# ProPrj_Transist_rle_Led_Kontrol_Devresi_.net
KiCad netlist of a schematic drawn in EasyEDA Pro
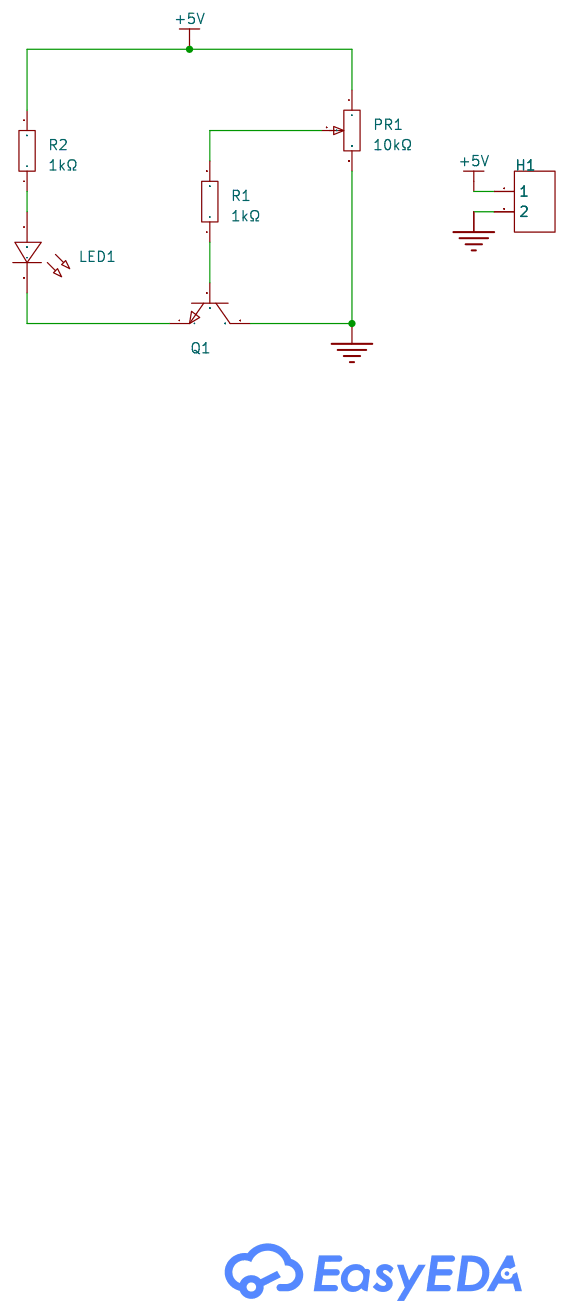
[diagram p0: schematic sheet]

(export (version "E")
  (design (tool "Eeschema 10.0.6"))
  (components
    (comp (ref "H1")
      (value "~")
      (footprint "easyedapro:HDR-TH_2P-P2.54-V-F")
      (fields (field (name "Manufacturer Part") "2.54-1*2P母") (field (name "Manufacturer") "BOOMELE(博穆精密)"))
      (libsource (lib "easyedapro") (part "Header-Female-2.54_1x2"))
    )
    (comp (ref "LED1")
      (value "~")
      (footprint "easyedapro:LED_TH-3mm")
      (libsource (lib "easyedapro") (part "LED_TH-R"))
    )
    (comp (ref "PR1")
      (value "10kΩ")
      (footprint "easyedapro:R_3296")
      (libsource (lib "easyedapro") (part "R_3296"))
    )
    (comp (ref "Q1")
      (value "~")
      (footprint "easyedapro:S8050_TO_92")
      (libsource (lib "easyedapro") (part "S8050_TO_NPN"))
    )
    (comp (ref "R1")
      (value "1kΩ")
      (footprint "easyedapro:Res_1/4W")
      (libsource (lib "easyedapro") (part "电阻"))
    )
    (comp (ref "R2")
      (value "1kΩ")
      (footprint "easyedapro:Res_1/4W")
      (libsource (lib "easyedapro") (part "电阻"))
    )
  )
  (nets
    (net (code "1") (name "+5V") (class "Default")
      (node (ref "H1") (pin "1") (pinfunction "1_1") (pintype "input"))
      (node (ref "PR1") (pin "1") (pinfunction "1_1") (pintype "input"))
      (node (ref "R2") (pin "2") (pinfunction "2_2") (pintype "input"))
    )
    (net (code "2") (name "GND") (class "Default")
      (node (ref "H1") (pin "2") (pinfunction "2_2") (pintype "input"))
      (node (ref "PR1") (pin "3") (pinfunction "3_3") (pintype "input"))
      (node (ref "Q1") (pin "3") (pinfunction "C_3") (pintype "unspecified"))
    )
    (net (code "3") (name "Net-(LED1-A)") (class "Default")
      (node (ref "LED1") (pin "2") (pinfunction "A_2") (pintype "input"))
      (node (ref "Q1") (pin "1") (pinfunction "E_1") (pintype "unspecified"))
    )
    (net (code "4") (name "Net-(LED1-C)") (class "Default")
      (node (ref "LED1") (pin "1") (pinfunction "C_1") (pintype "input"))
      (node (ref "R2") (pin "1") (pinfunction "1_1") (pintype "input"))
    )
    (net (code "5") (name "Net-(PR1-Pad2)") (class "Default")
      (node (ref "PR1") (pin "2") (pinfunction "2_2") (pintype "input"))
      (node (ref "R1") (pin "2") (pinfunction "2_2") (pintype "input"))
    )
    (net (code "6") (name "Net-(Q1-B)") (class "Default")
      (node (ref "Q1") (pin "2") (pinfunction "B_2") (pintype "unspecified"))
      (node (ref "R1") (pin "1") (pinfunction "1_1") (pintype "input"))
    )
  )
)
